# debugging_board_PFC161.net
KiCad netlist of a schematic drawn in Altium Designer
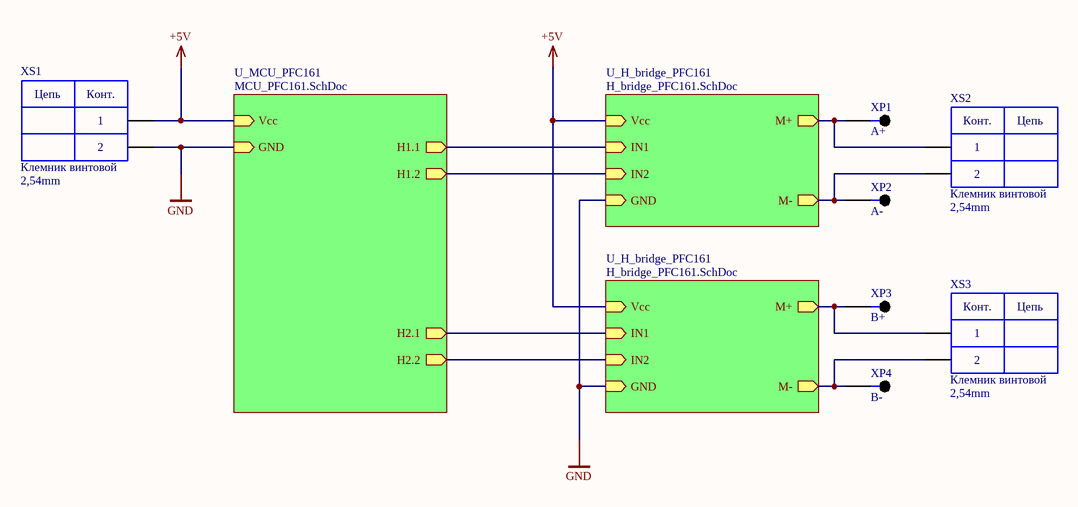
[diagram p0: debugging_board_PFC161.SchDoc]

(export (version "E")
  (design (tool "Eeschema 10.0.6"))
  (components
    (comp (ref "XP1")
      (value "A+")
      (footprint "XP_solder")
      (libsource (lib "MechanikLibrary") (part "XP_solder"))
    )
    (comp (ref "XP2")
      (value "A-")
      (footprint "XP_solder")
      (libsource (lib "MechanikLibrary") (part "XP_solder"))
    )
    (comp (ref "XP3")
      (value "B+")
      (footprint "XP_solder")
      (libsource (lib "MechanikLibrary") (part "XP_solder"))
    )
    (comp (ref "XP4")
      (value "B-")
      (footprint "XP_solder")
      (libsource (lib "MechanikLibrary") (part "XP_solder"))
    )
    (comp (ref "XS1")
      (value "Клемник винтовой")
      (footprint "XS_2x2.54MM")
      (fields (field (name "PACKAGE") "2,54mm"))
      (libsource (lib "MechanikLibrary") (part "Клемник винтовой 2-контактный, 2,54мм"))
    )
    (comp (ref "XS2")
      (value "Клемник винтовой")
      (footprint "XS_2x2.54MM")
      (fields (field (name "PACKAGE") "2,54mm"))
      (libsource (lib "MechanikLibrary") (part "Клемник винтовой 2-контактный, 2,54мм"))
    )
    (comp (ref "XS3")
      (value "Клемник винтовой")
      (footprint "XS_2x2.54MM")
      (fields (field (name "PACKAGE") "2,54mm"))
      (libsource (lib "MechanikLibrary") (part "Клемник винтовой 2-контактный, 2,54мм"))
    )
  )
  (nets
    (net (code "1") (name "+5V") (class "Default") (node (ref "XS1") (pin "1") (pintype "passive")))
    (net (code "6") (name "/M+") (class "Default")
      (node (ref "XP1") (pin "1") (pinfunction "1_1") (pintype "passive"))
      (node (ref "XS2") (pin "1") (pintype "passive"))
    )
    (net (code "7") (name "/M+_1") (class "Default")
      (node (ref "XP3") (pin "1") (pinfunction "1_1") (pintype "passive"))
      (node (ref "XS3") (pin "1") (pintype "passive"))
    )
    (net (code "8") (name "/M-") (class "Default")
      (node (ref "XP2") (pin "1") (pinfunction "1_1") (pintype "passive"))
      (node (ref "XS2") (pin "2") (pintype "passive"))
    )
    (net (code "9") (name "/M-_1") (class "Default")
      (node (ref "XP4") (pin "1") (pinfunction "1_1") (pintype "passive"))
      (node (ref "XS3") (pin "2") (pintype "passive"))
    )
    (net (code "10") (name "GND") (class "Default") (node (ref "XS1") (pin "2") (pintype "passive")))
  )
)
